# Selection.net
KiCad netlist of a schematic drawn in Altium Designer
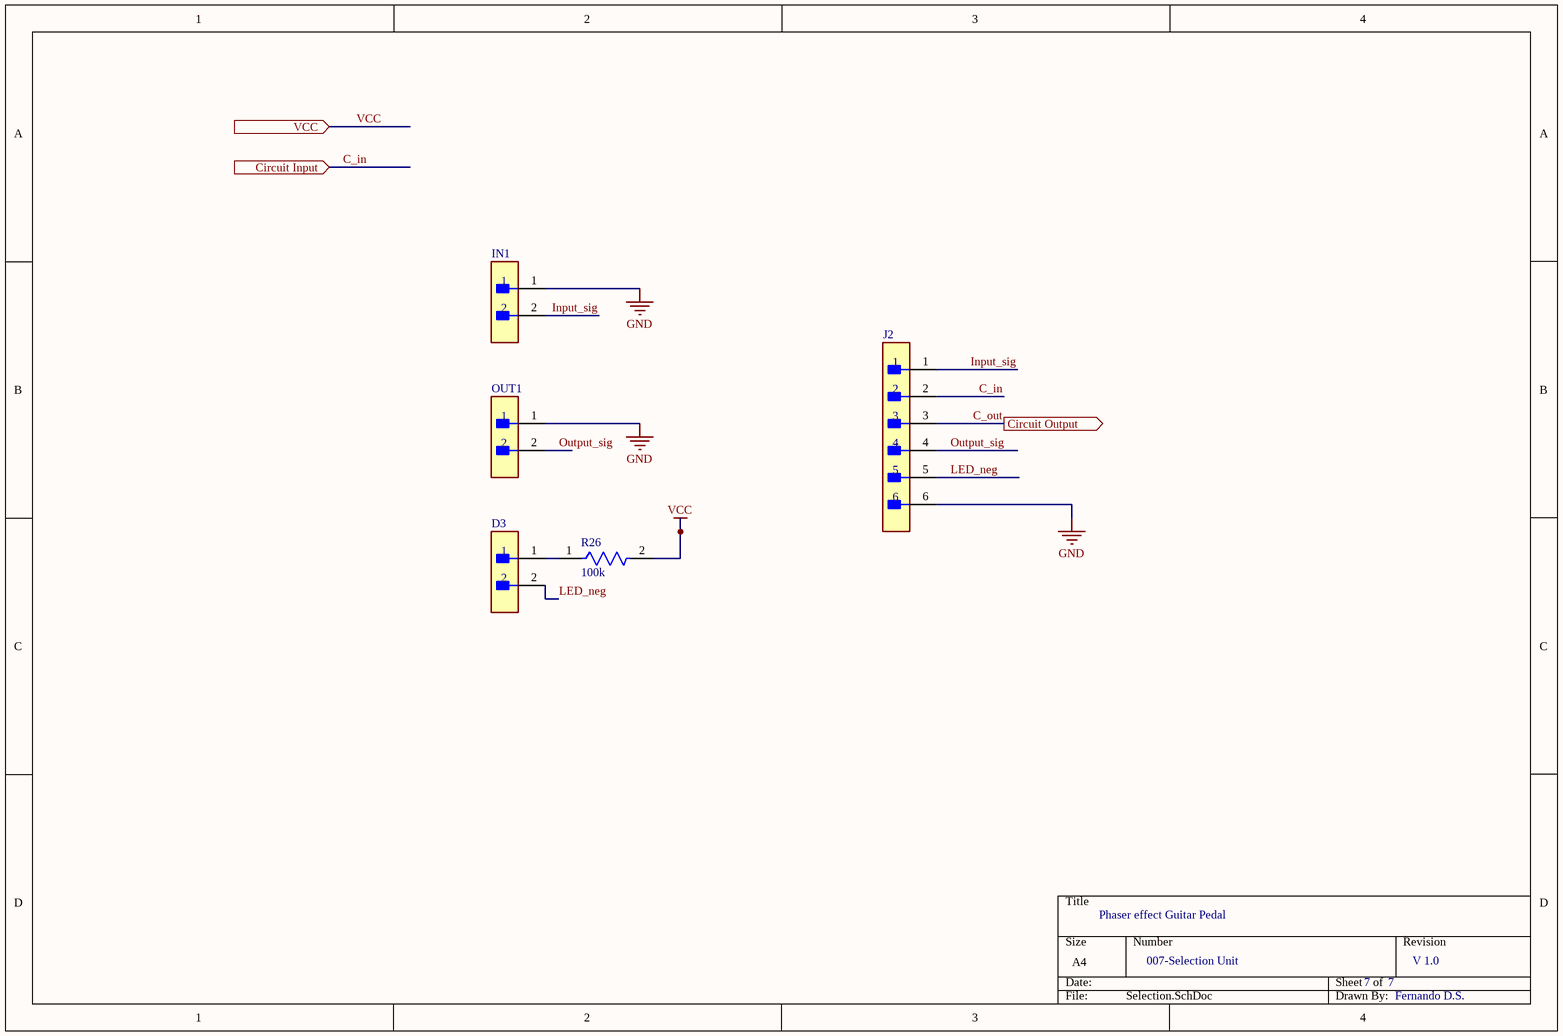
[diagram p0: Selection.SchDoc]

(export (version "E")
  (design (tool "Eeschema 10.0.6"))
  (components
    (comp (ref "D3")
      (value "B2B-EH-A(LF)(SN)")
      (footprint "FP-B2B-EH-A_LF_SN-MFG")
      (description "CONN HEADER VERT 2POS 2.5MM")
      (libsource (lib "Altium Content Vault") (part "3bc925449376181038e59eaffc5286c"))
    )
    (comp (ref "IN1")
      (value "B2B-EH-A(LF)(SN)")
      (footprint "FP-B2B-EH-A_LF_SN-MFG")
      (description "CONN HEADER VERT 2POS 2.5MM")
      (libsource (lib "Altium Content Vault") (part "3bc925449376181038e59eaffc5286c"))
    )
    (comp (ref "J2")
      (value "B6B-XH-A(LF)(SN)")
      (footprint "FP-B6B-XH-A_LF_SN-MFG")
      (description "CONN HEADER VERT 6POS 2.5MM")
      (libsource (lib "Altium Content Vault") (part "f2cb566baf1c37ab5a3b8e90bbeafd6"))
    )
    (comp (ref "OUT1")
      (value "B2B-EH-A(LF)(SN)")
      (footprint "FP-B2B-EH-A_LF_SN-MFG")
      (description "CONN HEADER VERT 2POS 2.5MM")
      (libsource (lib "Altium Content Vault") (part "3bc925449376181038e59eaffc5286c"))
    )
    (comp (ref "R26")
      (value "100k")
      (footprint "FP-MRS25-MFG")
      (fields (field (name "TOLERANCE") "1%"))
      (libsource (lib "Altium Content Vault") (part "1029c3af85768c4190bb7ad29bc67b5"))
    )
  )
  (nets
    (net (code "1") (name "/C_in") (class "Default")
      (node (ref "J2") (pin "2") (pinfunction "2_2") (pintype "passive"))
    )
    (net (code "2") (name "/C_out") (class "Default")
      (node (ref "J2") (pin "3") (pinfunction "3_3") (pintype "passive"))
    )
    (net (code "3") (name "/Input_sig") (class "Default")
      (node (ref "IN1") (pin "2") (pinfunction "2_2") (pintype "passive"))
      (node (ref "J2") (pin "1") (pinfunction "1_1") (pintype "passive"))
    )
    (net (code "4") (name "/LED_neg") (class "Default")
      (node (ref "D3") (pin "2") (pinfunction "2_2") (pintype "passive"))
      (node (ref "J2") (pin "5") (pinfunction "5_5") (pintype "passive"))
    )
    (net (code "5") (name "/Output_sig") (class "Default")
      (node (ref "J2") (pin "4") (pinfunction "4_4") (pintype "passive"))
      (node (ref "OUT1") (pin "2") (pinfunction "2_2") (pintype "passive"))
    )
    (net (code "6") (name "GND") (class "Default")
      (node (ref "IN1") (pin "1") (pinfunction "1_1") (pintype "passive"))
      (node (ref "J2") (pin "6") (pinfunction "6_6") (pintype "passive"))
      (node (ref "OUT1") (pin "1") (pinfunction "1_1") (pintype "passive"))
    )
    (net (code "7") (name "Net-(D3-Pad1)") (class "Default")
      (node (ref "D3") (pin "1") (pinfunction "1_1") (pintype "passive"))
      (node (ref "R26") (pin "1") (pinfunction "1_1") (pintype "passive"))
    )
    (net (code "8") (name "VCC") (class "Default")
      (node (ref "R26") (pin "2") (pinfunction "2_2") (pintype "passive"))
    )
  )
)
